# design.net
KiCad netlist of a schematic drawn in Altium Designer
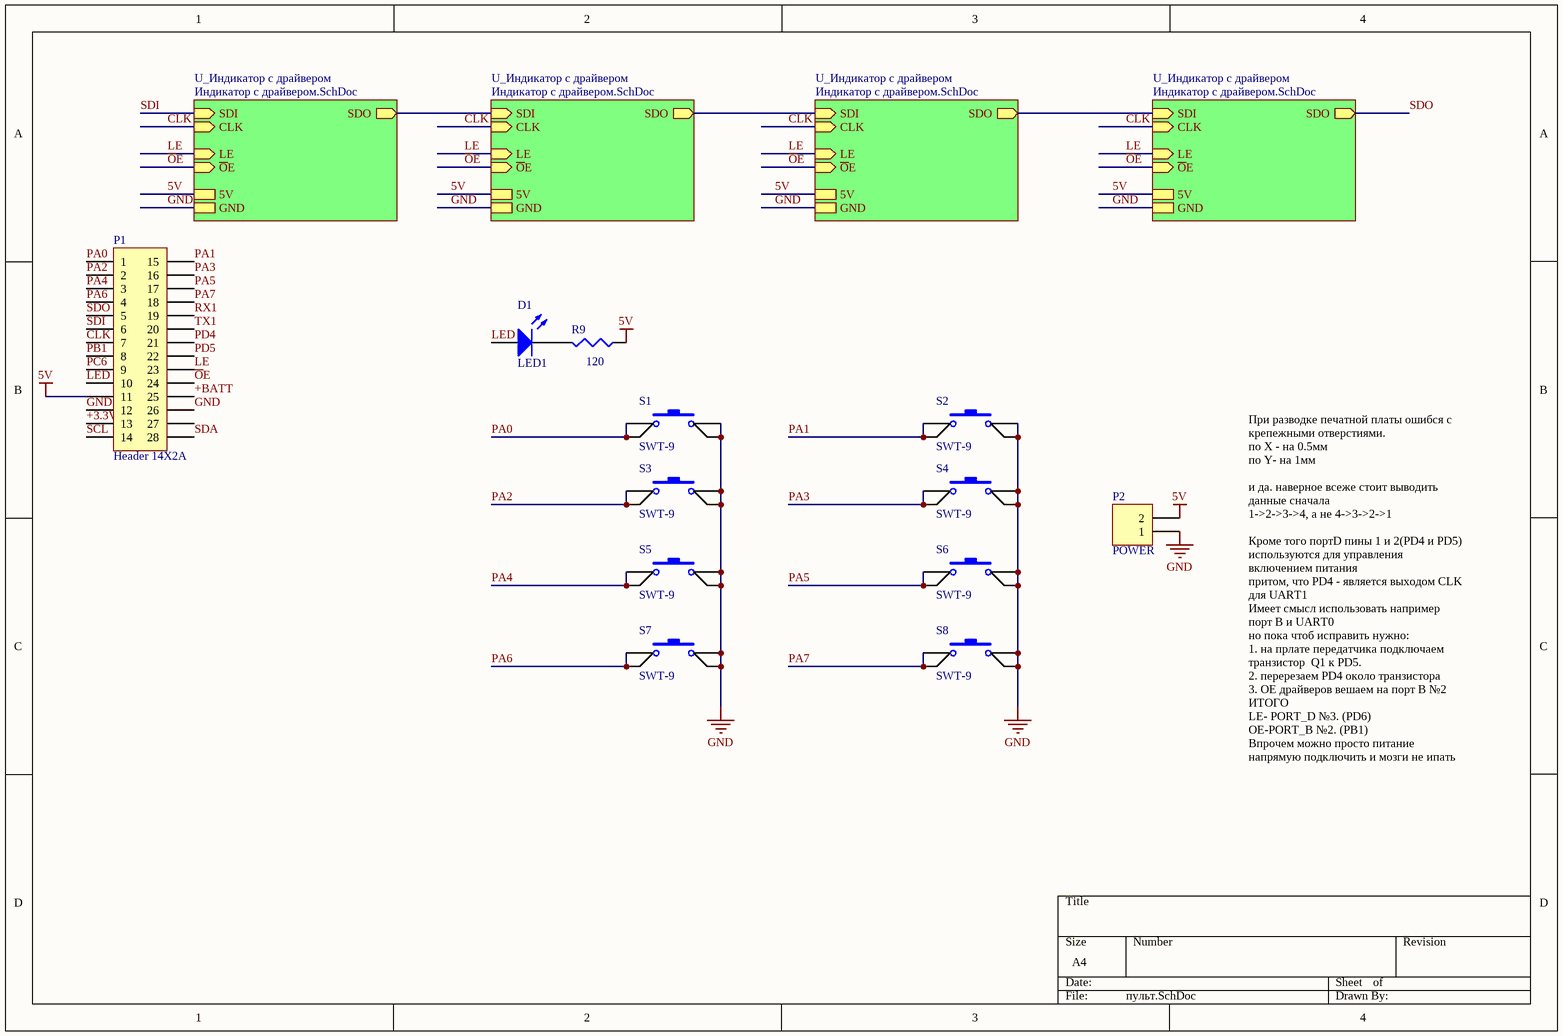
[diagram p0: пульт.SchDoc]

(export (version "E")
  (design (tool "Eeschema 10.0.6"))
  (components
    (comp (ref "D1")
      (value "LED1")
      (footprint "LED-1")
      (description "Typical RED GaAs LED")
      (fields (field (name "PUBLISHER") "Altium Limited"))
      (libsource (lib "Miscellaneous Devices") (part "LED1"))
    )
    (comp (ref "P1")
      (value "Header 14X2A")
      (footprint "HDR2X14_CEN")
      (description "Header, 14-Pin, Dual row")
      (fields (field (name "PUBLISHER") "Altium Limited"))
      (libsource (lib "Miscellaneous Connectors") (part "Header 14X2A"))
    )
    (comp (ref "P2")
      (value "POWER")
      (footprint "HDR1X2H")
      (description "Header, 2-Pin, Right Angle")
      (fields (field (name "PUBLISHER") "Altium Limited"))
      (libsource (lib "Miscellaneous Connectors") (part "Header 2H"))
    )
    (comp (ref "R9")
      (value "120")
      (footprint "RESC1608L")
      (description "Resistor")
      (fields (field (name "Comment") "Res3") (field (name "PUBLISHER") "Altium Limited"))
      (libsource (lib "Miscellaneous Devices") (part "Res3"))
    )
    (comp (ref "S1")
      (value "SWT-9")
      (footprint "SWT-9")
      (description "Switch")
      (libsource (lib "LibX") (part "SWT-9"))
    )
    (comp (ref "S2")
      (value "SWT-9")
      (footprint "SWT-9")
      (description "Switch")
      (libsource (lib "LibX") (part "SWT-9"))
    )
    (comp (ref "S3")
      (value "SWT-9")
      (footprint "SWT-9")
      (description "Switch")
      (libsource (lib "LibX") (part "SWT-9"))
    )
    (comp (ref "S4")
      (value "SWT-9")
      (footprint "SWT-9")
      (description "Switch")
      (libsource (lib "LibX") (part "SWT-9"))
    )
    (comp (ref "S5")
      (value "SWT-9")
      (footprint "SWT-9")
      (description "Switch")
      (libsource (lib "LibX") (part "SWT-9"))
    )
    (comp (ref "S6")
      (value "SWT-9")
      (footprint "SWT-9")
      (description "Switch")
      (libsource (lib "LibX") (part "SWT-9"))
    )
    (comp (ref "S7")
      (value "SWT-9")
      (footprint "SWT-9")
      (description "Switch")
      (libsource (lib "LibX") (part "SWT-9"))
    )
    (comp (ref "S8")
      (value "SWT-9")
      (footprint "SWT-9")
      (description "Switch")
      (libsource (lib "LibX") (part "SWT-9"))
    )
  )
  (nets
    (net (code "1") (name "/+3.3V") (class "Default")
      (node (ref "P1") (pin "13") (pinfunction "13_13") (pintype "passive"))
    )
    (net (code "2") (name "/+BATT") (class "Default")
      (node (ref "P1") (pin "25") (pinfunction "25_25") (pintype "passive"))
    )
    (net (code "3") (name "/CLK") (class "Default")
      (node (ref "P1") (pin "7") (pinfunction "7_7") (pintype "passive"))
    )
    (net (code "4") (name "/LE") (class "Default")
      (node (ref "P1") (pin "23") (pinfunction "23_23") (pintype "passive"))
    )
    (net (code "5") (name "/LED") (class "Default")
      (node (ref "D1") (pin "1") (pinfunction "A_1") (pintype "passive"))
      (node (ref "P1") (pin "10") (pinfunction "10_10") (pintype "passive"))
    )
    (net (code "6") (name "/PA0") (class "Default")
      (node (ref "P1") (pin "1") (pinfunction "1_1") (pintype "passive"))
      (node (ref "S1") (pin "1") (pinfunction "1_1") (pintype "passive"))
      (node (ref "S1") (pin "2") (pinfunction "2_2") (pintype "passive"))
    )
    (net (code "7") (name "/PA1") (class "Default")
      (node (ref "P1") (pin "15") (pinfunction "15_15") (pintype "passive"))
      (node (ref "S2") (pin "1") (pinfunction "1_1") (pintype "passive"))
      (node (ref "S2") (pin "2") (pinfunction "2_2") (pintype "passive"))
    )
    (net (code "8") (name "/PA2") (class "Default")
      (node (ref "P1") (pin "2") (pinfunction "2_2") (pintype "passive"))
      (node (ref "S3") (pin "1") (pinfunction "1_1") (pintype "passive"))
      (node (ref "S3") (pin "2") (pinfunction "2_2") (pintype "passive"))
    )
    (net (code "9") (name "/PA3") (class "Default")
      (node (ref "P1") (pin "16") (pinfunction "16_16") (pintype "passive"))
      (node (ref "S4") (pin "1") (pinfunction "1_1") (pintype "passive"))
      (node (ref "S4") (pin "2") (pinfunction "2_2") (pintype "passive"))
    )
    (net (code "10") (name "/PA4") (class "Default")
      (node (ref "P1") (pin "3") (pinfunction "3_3") (pintype "passive"))
      (node (ref "S5") (pin "1") (pinfunction "1_1") (pintype "passive"))
      (node (ref "S5") (pin "2") (pinfunction "2_2") (pintype "passive"))
    )
    (net (code "11") (name "/PA5") (class "Default")
      (node (ref "P1") (pin "17") (pinfunction "17_17") (pintype "passive"))
      (node (ref "S6") (pin "1") (pinfunction "1_1") (pintype "passive"))
      (node (ref "S6") (pin "2") (pinfunction "2_2") (pintype "passive"))
    )
    (net (code "12") (name "/PA6") (class "Default")
      (node (ref "P1") (pin "4") (pinfunction "4_4") (pintype "passive"))
      (node (ref "S7") (pin "1") (pinfunction "1_1") (pintype "passive"))
      (node (ref "S7") (pin "2") (pinfunction "2_2") (pintype "passive"))
    )
    (net (code "13") (name "/PA7") (class "Default")
      (node (ref "P1") (pin "18") (pinfunction "18_18") (pintype "passive"))
      (node (ref "S8") (pin "1") (pinfunction "1_1") (pintype "passive"))
      (node (ref "S8") (pin "2") (pinfunction "2_2") (pintype "passive"))
    )
    (net (code "14") (name "/PB1") (class "Default")
      (node (ref "P1") (pin "8") (pinfunction "8_8") (pintype "passive"))
    )
    (net (code "15") (name "/PC6") (class "Default")
      (node (ref "P1") (pin "9") (pinfunction "9_9") (pintype "passive"))
    )
    (net (code "16") (name "/PD4") (class "Default")
      (node (ref "P1") (pin "21") (pinfunction "21_21") (pintype "passive"))
    )
    (net (code "17") (name "/PD5") (class "Default")
      (node (ref "P1") (pin "22") (pinfunction "22_22") (pintype "passive"))
    )
    (net (code "18") (name "/RX1") (class "Default")
      (node (ref "P1") (pin "19") (pinfunction "19_19") (pintype "passive"))
    )
    (net (code "19") (name "/SCL") (class "Default")
      (node (ref "P1") (pin "14") (pinfunction "14_14") (pintype "passive"))
    )
    (net (code "20") (name "/SDA") (class "Default")
      (node (ref "P1") (pin "28") (pinfunction "28_28") (pintype "passive"))
    )
    (net (code "21") (name "/SDI") (class "Default")
      (node (ref "P1") (pin "6") (pinfunction "6_6") (pintype "passive"))
    )
    (net (code "22") (name "/SDO") (class "Default")
      (node (ref "P1") (pin "5") (pinfunction "5_5") (pintype "passive"))
    )
    (net (code "26") (name "/TX1") (class "Default")
      (node (ref "P1") (pin "20") (pinfunction "20_20") (pintype "passive"))
    )
    (net (code "27") (name "/~{O}E") (class "Default")
      (node (ref "P1") (pin "24") (pinfunction "24_24") (pintype "passive"))
    )
    (net (code "28") (name "5V") (class "Default")
      (node (ref "P1") (pin "11") (pinfunction "11_11") (pintype "passive"))
      (node (ref "P2") (pin "2") (pinfunction "2_2") (pintype "passive"))
      (node (ref "R9") (pin "1") (pinfunction "1_1") (pintype "passive"))
    )
    (net (code "29") (name "GND") (class "Default")
      (node (ref "P1") (pin "12") (pinfunction "12_12") (pintype "passive"))
      (node (ref "P1") (pin "26") (pinfunction "26_26") (pintype "passive"))
      (node (ref "P2") (pin "1") (pinfunction "1_1") (pintype "passive"))
      (node (ref "S1") (pin "3") (pinfunction "3_3") (pintype "passive"))
      (node (ref "S1") (pin "4") (pinfunction "4_4") (pintype "passive"))
      (node (ref "S2") (pin "3") (pinfunction "3_3") (pintype "passive"))
      (node (ref "S2") (pin "4") (pinfunction "4_4") (pintype "passive"))
      (node (ref "S3") (pin "3") (pinfunction "3_3") (pintype "passive"))
      (node (ref "S3") (pin "4") (pinfunction "4_4") (pintype "passive"))
      (node (ref "S4") (pin "3") (pinfunction "3_3") (pintype "passive"))
      (node (ref "S4") (pin "4") (pinfunction "4_4") (pintype "passive"))
      (node (ref "S5") (pin "3") (pinfunction "3_3") (pintype "passive"))
      (node (ref "S5") (pin "4") (pinfunction "4_4") (pintype "passive"))
      (node (ref "S6") (pin "3") (pinfunction "3_3") (pintype "passive"))
      (node (ref "S6") (pin "4") (pinfunction "4_4") (pintype "passive"))
      (node (ref "S7") (pin "3") (pinfunction "3_3") (pintype "passive"))
      (node (ref "S7") (pin "4") (pinfunction "4_4") (pintype "passive"))
      (node (ref "S8") (pin "3") (pinfunction "3_3") (pintype "passive"))
      (node (ref "S8") (pin "4") (pinfunction "4_4") (pintype "passive"))
    )
    (net (code "30") (name "Net-(D1-K)") (class "Default")
      (node (ref "D1") (pin "2") (pinfunction "K_2") (pintype "passive"))
      (node (ref "R9") (pin "2") (pinfunction "2_2") (pintype "passive"))
    )
    (net (code "31") (name "unconnected-(P1-Pad27)") (class "Default")
      (node (ref "P1") (pin "27") (pinfunction "27_27") (pintype "passive"))
    )
  )
)
